# QSPI_FLASH.net
KiCad netlist of a schematic drawn in Altium Designer
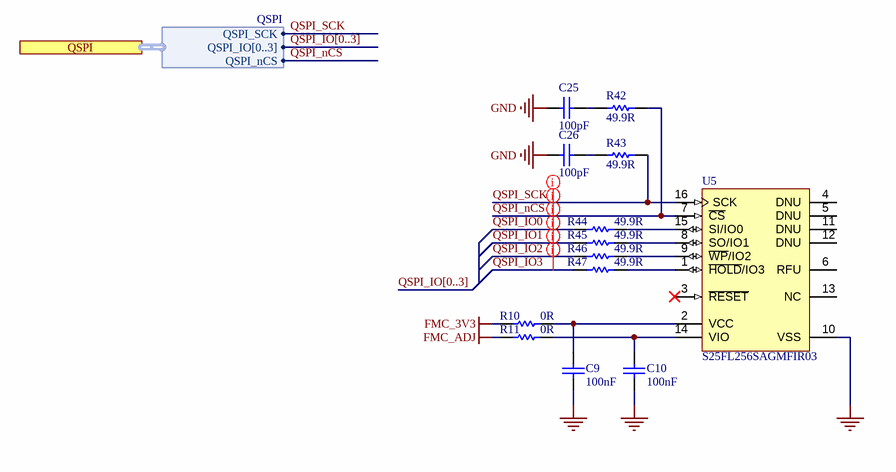
[diagram p0: QSPI_FLASH.SchDoc]

(export (version "E")
  (design (tool "Eeschema 10.0.6"))
  (components
    (comp (ref "C9")
      (value "100nF")
      (footprint "CAPC1050X55X23LL05T13")
      (description "Chip Capacitor, 100 nF, +/- 10%, 16 V, -55 to 125 degC, 0402 (1005 Metric), RoHS, Tape and Reel")
      (fields
        (field (name "MANUFACTURER") "Samsung Electro-Mechanics")
        (field (name "MANUFACTURER PART NUMBER") "CL05B104KO5NNNC")
      )
      (libsource (lib "Altium Content Vault") (part "CAP-NP-2"))
    )
    (comp (ref "C10")
      (value "100nF")
      (footprint "CAPC1050X55X23LL05T13")
      (description "Chip Capacitor, 100 nF, +/- 10%, 16 V, -55 to 125 degC, 0402 (1005 Metric), RoHS, Tape and Reel")
      (fields
        (field (name "MANUFACTURER") "Samsung Electro-Mechanics")
        (field (name "MANUFACTURER PART NUMBER") "CL05B104KO5NNNC")
      )
      (libsource (lib "Altium Content Vault") (part "CAP-NP-2"))
    )
    (comp (ref "C25")
      (value "100pF")
      (footprint "CAPC0603X33X15LL03T05")
      (fields
        (field (name "PART NUMBER") "0201YC101KAT2A")
        (field (name "MANUFACTURER") "AVX Interconnect / Elco")
        (field (name "TOLERANCE") "10%")
      )
      (libsource (lib "Altium Content Vault") (part "CAP"))
    )
    (comp (ref "C26")
      (value "100pF")
      (footprint "CAPC0603X33X15LL03T05")
      (fields
        (field (name "PART NUMBER") "0201YC101KAT2A")
        (field (name "MANUFACTURER") "AVX Interconnect / Elco")
        (field (name "TOLERANCE") "10%")
      )
      (libsource (lib "Altium Content Vault") (part "CAP"))
    )
    (comp (ref "R10")
      (value "0R")
      (footprint "RESC1005X40X25LL05T10")
      (fields
        (field (name "MANUFACTURER") "Yageo")
        (field (name "PART NUMBER") "RC0402JR-070RL")
        (field (name "TOLERANCE") "5%")
      )
      (libsource (lib "Altium Content Vault") (part "RES"))
    )
    (comp (ref "R11")
      (value "0R")
      (footprint "RESC1005X40X25LL05T10")
      (fields
        (field (name "MANUFACTURER") "Yageo")
        (field (name "PART NUMBER") "RC0402JR-070RL")
        (field (name "TOLERANCE") "5%")
      )
      (libsource (lib "Altium Content Vault") (part "RES"))
    )
    (comp (ref "R42")
      (value "49.9R")
      (footprint "RESC0603X26X15LL03T05")
      (fields
        (field (name "MANUFACTURER") "Panasonic")
        (field (name "PART NUMBER") "ERJ-1GEF49R9C")
        (field (name "TOLERANCE") "1%")
      )
      (libsource (lib "Altium Content Vault") (part "RES"))
    )
    (comp (ref "R43")
      (value "49.9R")
      (footprint "RESC0603X26X15LL03T05")
      (fields
        (field (name "MANUFACTURER") "Panasonic")
        (field (name "PART NUMBER") "ERJ-1GEF49R9C")
        (field (name "TOLERANCE") "1%")
      )
      (libsource (lib "Altium Content Vault") (part "RES"))
    )
    (comp (ref "R44")
      (value "49.9R")
      (footprint "RESC0603X26X15LL03T05")
      (fields
        (field (name "MANUFACTURER") "Panasonic")
        (field (name "PART NUMBER") "ERJ-1GEF49R9C")
        (field (name "TOLERANCE") "1%")
      )
      (libsource (lib "Altium Content Vault") (part "RES"))
    )
    (comp (ref "R45")
      (value "49.9R")
      (footprint "RESC0603X26X15LL03T05")
      (fields
        (field (name "MANUFACTURER") "Panasonic")
        (field (name "PART NUMBER") "ERJ-1GEF49R9C")
        (field (name "TOLERANCE") "1%")
      )
      (libsource (lib "Altium Content Vault") (part "RES"))
    )
    (comp (ref "R46")
      (value "49.9R")
      (footprint "RESC0603X26X15LL03T05")
      (fields
        (field (name "MANUFACTURER") "Panasonic")
        (field (name "PART NUMBER") "ERJ-1GEF49R9C")
        (field (name "TOLERANCE") "1%")
      )
      (libsource (lib "Altium Content Vault") (part "RES"))
    )
    (comp (ref "R47")
      (value "49.9R")
      (footprint "RESC0603X26X15LL03T05")
      (fields
        (field (name "MANUFACTURER") "Panasonic")
        (field (name "PART NUMBER") "ERJ-1GEF49R9C")
        (field (name "TOLERANCE") "1%")
      )
      (libsource (lib "Altium Content Vault") (part "RES"))
    )
    (comp (ref "U5")
      (value "S25FL256SAGMFIR03")
      (footprint "SOIC127P1030X265-16N")
      (description "NOR Flash Serial-SPI 3V 256M-bit 256M x 1bit 8ns 16-Pin SOIC")
      (fields (field (name "MANUFACTURER") "Cypress Semiconductor Corp"))
      (libsource (lib "ETHZ Vault") (part "CMP-00165-1"))
    )
  )
  (nets
    (net (code "2") (name "/QSPI_IO0") (class "Default")
      (node (ref "R44") (pin "2") (pinfunction "2_2") (pintype "passive"))
    )
    (net (code "3") (name "/QSPI_IO1") (class "Default")
      (node (ref "R45") (pin "2") (pinfunction "2_2") (pintype "passive"))
    )
    (net (code "4") (name "/QSPI_IO2") (class "Default")
      (node (ref "R46") (pin "2") (pinfunction "2_2") (pintype "passive"))
    )
    (net (code "5") (name "/QSPI_IO3") (class "Default")
      (node (ref "R47") (pin "2") (pinfunction "2_2") (pintype "passive"))
    )
    (net (code "7") (name "/QSPI_SCK") (class "Default")
      (node (ref "R43") (pin "1") (pinfunction "1_1") (pintype "passive"))
      (node (ref "U5") (pin "16") (pinfunction "SCK_16") (pintype "input"))
    )
    (net (code "8") (name "/QSPI_nCS") (class "Default")
      (node (ref "R42") (pin "1") (pinfunction "1_1") (pintype "passive"))
      (node (ref "U5") (pin "7") (pinfunction "~{CS}_7") (pintype "input"))
    )
    (net (code "11") (name "FMC_3V3") (class "Default")
      (node (ref "R10") (pin "2") (pinfunction "2_2") (pintype "passive"))
    )
    (net (code "12") (name "FMC_ADJ") (class "Default")
      (node (ref "R11") (pin "2") (pinfunction "2_2") (pintype "passive"))
    )
    (net (code "13") (name "GND") (class "Default")
      (node (ref "C10") (pin "1") (pinfunction "1_1") (pintype "passive"))
      (node (ref "C25") (pin "2") (pinfunction "2_2") (pintype "passive"))
      (node (ref "C26") (pin "2") (pinfunction "2_2") (pintype "passive"))
      (node (ref "C9") (pin "1") (pinfunction "1_1") (pintype "passive"))
      (node (ref "U5") (pin "10") (pinfunction "VSS_10") (pintype "power_in"))
    )
    (net (code "14") (name "Net-(C25-Pad1)") (class "Default")
      (node (ref "C25") (pin "1") (pinfunction "1_1") (pintype "passive"))
      (node (ref "R42") (pin "2") (pinfunction "2_2") (pintype "passive"))
    )
    (net (code "15") (name "Net-(C26-Pad1)") (class "Default")
      (node (ref "C26") (pin "1") (pinfunction "1_1") (pintype "passive"))
      (node (ref "R43") (pin "2") (pinfunction "2_2") (pintype "passive"))
    )
    (net (code "16") (name "Net-(U5-SI{slash}IO0)") (class "Default")
      (node (ref "R44") (pin "1") (pinfunction "1_1") (pintype "passive"))
      (node (ref "U5") (pin "15") (pinfunction "SI/IO0_15") (pintype "bidirectional"))
    )
    (net (code "17") (name "Net-(U5-SO{slash}IO1)") (class "Default")
      (node (ref "R45") (pin "1") (pinfunction "1_1") (pintype "passive"))
      (node (ref "U5") (pin "8") (pinfunction "SO/IO1_8") (pintype "bidirectional"))
    )
    (net (code "18") (name "Net-(U5-VCC)") (class "Default")
      (node (ref "C9") (pin "2") (pinfunction "2_2") (pintype "passive"))
      (node (ref "R10") (pin "1") (pinfunction "1_1") (pintype "passive"))
      (node (ref "U5") (pin "2") (pinfunction "VCC_2") (pintype "power_in"))
    )
    (net (code "19") (name "Net-(U5-VIO)") (class "Default")
      (node (ref "C10") (pin "2") (pinfunction "2_2") (pintype "passive"))
      (node (ref "R11") (pin "1") (pinfunction "1_1") (pintype "passive"))
      (node (ref "U5") (pin "14") (pinfunction "VIO_14") (pintype "power_in"))
    )
    (net (code "20") (name "Net-(U5-~{HOLD}{slash}IO3)") (class "Default")
      (node (ref "R47") (pin "1") (pinfunction "1_1") (pintype "passive"))
      (node (ref "U5") (pin "1") (pinfunction "~{HOLD}/IO3_1") (pintype "bidirectional"))
    )
    (net (code "21") (name "Net-(U5-~{WP}{slash}IO2)") (class "Default")
      (node (ref "R46") (pin "1") (pinfunction "1_1") (pintype "passive"))
      (node (ref "U5") (pin "9") (pinfunction "~{WP}/IO2_9") (pintype "bidirectional"))
    )
    (net (code "22") (name "unconnected-(U5-DNU-Pad4)") (class "Default")
      (node (ref "U5") (pin "4") (pinfunction "DNU_4") (pintype "passive"))
    )
    (net (code "23") (name "unconnected-(U5-DNU-Pad5)") (class "Default")
      (node (ref "U5") (pin "5") (pinfunction "DNU_5") (pintype "passive"))
    )
    (net (code "24") (name "unconnected-(U5-DNU-Pad11)") (class "Default")
      (node (ref "U5") (pin "11") (pinfunction "DNU_11") (pintype "passive"))
    )
    (net (code "25") (name "unconnected-(U5-DNU-Pad12)") (class "Default")
      (node (ref "U5") (pin "12") (pinfunction "DNU_12") (pintype "passive"))
    )
    (net (code "26") (name "unconnected-(U5-NC-Pad13)") (class "Default")
      (node (ref "U5") (pin "13") (pinfunction "NC_13") (pintype "passive"))
    )
    (net (code "27") (name "unconnected-(U5-RFU-Pad6)") (class "Default")
      (node (ref "U5") (pin "6") (pinfunction "RFU_6") (pintype "passive"))
    )
    (net (code "28") (name "unconnected-(U5-~{RESET}-Pad3)") (class "Default")
      (node (ref "U5") (pin "3") (pinfunction "~{RESET}_3") (pintype "input+no_connect"))
    )
  )
)
